# MCU.net
KiCad netlist of a schematic drawn in Altium Designer
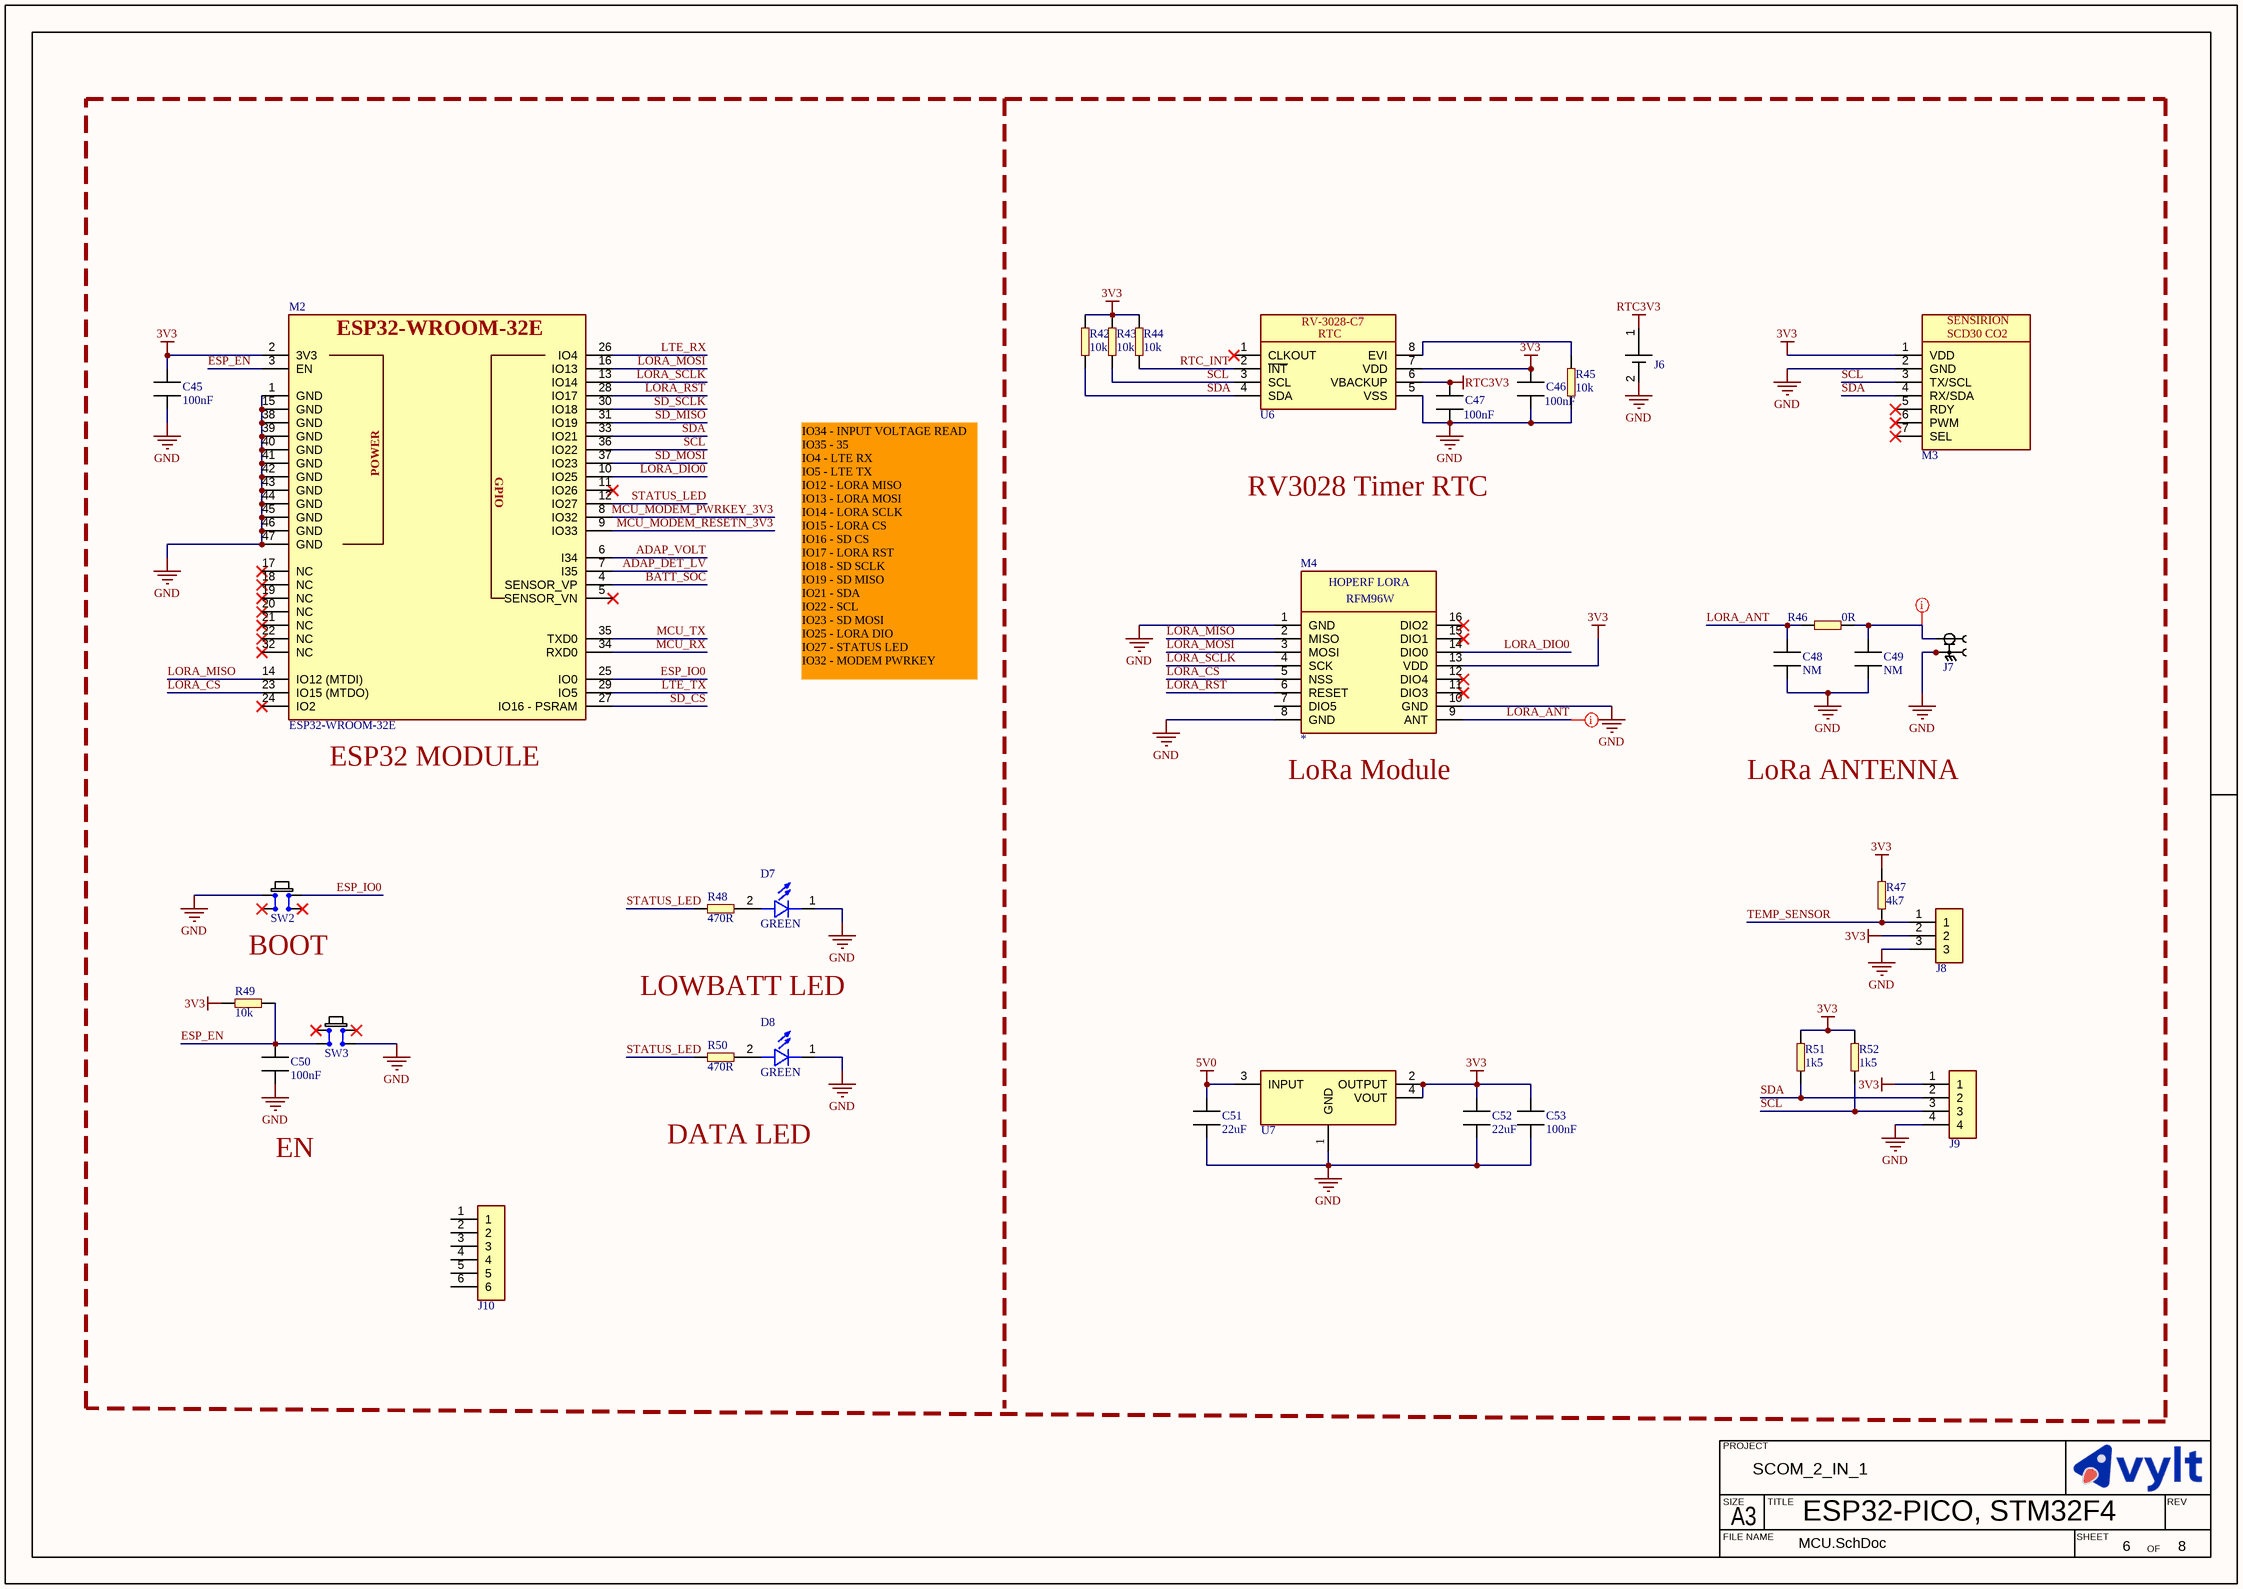
[diagram p0: MCU.SchDoc]

(export (version "E")
  (design (tool "Eeschema 10.0.6"))
  (components
    (comp (ref "C45")
      (value "100nF")
      (footprint "CAPC2012X13L")
      (description "Chip Capacitor, 2-Leads, Body 2.00x1.25mm, IPC High Density")
      (fields (field (name "Comment") "MLCC_0805"))
      (libsource (lib "Capacitor") (part "MLCC_0805"))
    )
    (comp (ref "C46")
      (value "100nF")
      (footprint "CAPC2012X13L")
      (description "1uF 105 0805 (2012 metric) 50V X7R MLCC SMD")
      (fields (field (name "Comment") "MLCC_0805"))
      (libsource (lib "Capacitor") (part "MLCC_0805"))
    )
    (comp (ref "C47")
      (value "100nF")
      (footprint "CAPC2012X13L")
      (description "1uF 105 0805 (2012 metric) 50V X7R MLCC SMD")
      (fields (field (name "Comment") "MLCC_0805"))
      (libsource (lib "Capacitor") (part "MLCC_0805"))
    )
    (comp (ref "C48")
      (value "NM")
      (footprint "CAPC0603X03L")
      (description "Chip Capacitor, 2-Leads, Body 0.60x0.30mm, IPC High Density")
      (fields (field (name "Comment") "ERP_102-1"))
      (libsource (lib "Capacitor") (part "MLCC_0201"))
    )
    (comp (ref "C49")
      (value "NM")
      (footprint "CAPC0603X03L")
      (description "Chip Capacitor, 2-Leads, Body 0.60x0.30mm, IPC High Density")
      (fields (field (name "Comment") "ERP_102-1"))
      (libsource (lib "Capacitor") (part "MLCC_0201"))
    )
    (comp (ref "C50")
      (value "100nF")
      (footprint "CAPC2012X13L")
      (description "Chip Capacitor, 2-Leads, Body 2.00x1.25mm, IPC High Density")
      (fields (field (name "Comment") "MLCC_0805"))
      (libsource (lib "Capacitor") (part "MLCC_0805"))
    )
    (comp (ref "C51")
      (value "22uF")
      (footprint "CAPC2012X13L")
      (description "Chip Capacitor, 2-Leads, Body 2.00x1.25mm, IPC High Density")
      (fields (field (name "Comment") "MLCC_0805"))
      (libsource (lib "Capacitor") (part "MLCC_0805"))
    )
    (comp (ref "C52")
      (value "22uF")
      (footprint "CAPC2012X13L")
      (description "Chip Capacitor, 2-Leads, Body 2.00x1.25mm, IPC High Density")
      (fields (field (name "Comment") "MLCC_0805"))
      (libsource (lib "Capacitor") (part "MLCC_0805"))
    )
    (comp (ref "C53")
      (value "100nF")
      (footprint "CAPC2012X13L")
      (description "Chip Capacitor, 2-Leads, Body 2.00x1.25mm, IPC High Density")
      (fields (field (name "Comment") "MLCC_0805"))
      (libsource (lib "Capacitor") (part "MLCC_0805"))
    )
    (comp (ref "D7")
      (value "GREEN")
      (footprint "LED_1206")
      (description "LED CLEAR 1206 SMD")
      (fields (field (name "Comment") "LED_1206"))
      (libsource (lib "LED") (part "LED_1206"))
    )
    (comp (ref "D8")
      (value "GREEN")
      (footprint "LED_1206")
      (description "LED CLEAR 1206 SMD")
      (fields (field (name "Comment") "LED_1206"))
      (libsource (lib "LED") (part "LED_1206"))
    )
    (comp (ref "J6")
      (value "CR1220-BH")
      (footprint "CR1220-BH")
      (description "BATTERY HOLDER COIN 12.5MM SMD")
      (libsource (lib "Connectors") (part "CR1220-BH"))
    )
    (comp (ref "J7")
      (value "ERP_148-1")
      (footprint "uFL_50R")
      (description "uFL_50R")
      (libsource (lib "RF_Connector") (part "uFL_50R"))
    )
    (comp (ref "J8")
      (value "Terminal_Block_3Pin_5.08P")
      (footprint "TB_PLUG_5.08P_3P")
      (description "6PINS TERMINAL BLOCK 5.08 PITCH")
      (libsource (lib "Connectors") (part "Terminal_Block_3Pin_5.08P"))
    )
    (comp (ref "J9")
      (value "Terminal_Block_4Pin_5.08P")
      (footprint "TB_PLUG_5.08P_4P")
      (description "6PINS TERMINAL BLOCK 5.08 PITCH")
      (libsource (lib "Connectors") (part "Terminal_Block_4Pin_5.08P"))
    )
    (comp (ref "J10")
      (value "ERP_148-2")
      (footprint "6PX1R_F")
      (description "6PX1R Female Header")
      (libsource (lib "PinHeader") (part "6PX1R_F"))
    )
    (comp (ref "M2")
      (value "ESP32-WROOM-32E")
      (footprint "ESP32-WROOM-32UE")
      (description "ESP32-WROOM-32E Module")
      (libsource (lib "ESP") (part "ESP32-WROOM-32E"))
    )
    (comp (ref "M3")
      (value "SCD30")
      (footprint "SCD30")
      (description "CO₂ accuracy of ±(30 ppm + 3% MV) @400-10000 ppm")
      (libsource (lib "TemperatureSensor") (part "SCD30"))
    )
    (comp (ref "M4")
      (value "RFM96W")
      (footprint "RFM96W")
      (description "LoRa 868MHz SX1276 RF Transreceiver Module RFM96W")
      (fields (field (name "ALTIUM_VALUE") "*"))
      (libsource (lib "WirelessModule") (part "RFM96W"))
    )
    (comp (ref "R42")
      (value "10k")
      (footprint "RES_0603")
      (description "RES_0603")
      (fields (field (name "Comment") "ERP_101-1"))
      (libsource (lib "") (part "RES_0603_2"))
    )
    (comp (ref "R43")
      (value "10k")
      (footprint "RES_0603")
      (description "RES_0603")
      (fields (field (name "Comment") "ERP_101-1"))
      (libsource (lib "") (part "RES_0603_2"))
    )
    (comp (ref "R44")
      (value "10k")
      (footprint "RES_0603")
      (description "RES_0603")
      (fields (field (name "Comment") "ERP_101-1"))
      (libsource (lib "") (part "RES_0603_2"))
    )
    (comp (ref "R45")
      (value "10k")
      (footprint "RES_0603")
      (description "RES_0603")
      (fields (field (name "Comment") "ERP_101-1"))
      (libsource (lib "") (part "RES_0603_2"))
    )
    (comp (ref "R46")
      (value "0R")
      (footprint "RESC0603X03L")
      (description "RES_0201")
      (fields (field (name "Comment") "ERP_101-1"))
      (libsource (lib "Resistor") (part "RES_0201"))
    )
    (comp (ref "R47")
      (value "4k7")
      (footprint "RES_0603")
      (description "RES_0603")
      (fields (field (name "Comment") "ERP_101-1"))
      (libsource (lib "") (part "RES_0603_1"))
    )
    (comp (ref "R48")
      (value "470R")
      (footprint "RES_0603")
      (description "RES_0603")
      (fields (field (name "Comment") "ERP_101-1"))
      (libsource (lib "Resistor") (part "RES_0603"))
    )
    (comp (ref "R49")
      (value "10k")
      (footprint "RES_0603")
      (description "RES_0603")
      (fields (field (name "Comment") "ERP_101-1"))
      (libsource (lib "Resistor") (part "RES_0603"))
    )
    (comp (ref "R50")
      (value "470R")
      (footprint "RES_0603")
      (description "RES_0603")
      (fields (field (name "Comment") "ERP_101-1"))
      (libsource (lib "Resistor") (part "RES_0603"))
    )
    (comp (ref "R51")
      (value "1k5")
      (footprint "RES_0603")
      (description "RES_0603")
      (fields (field (name "Comment") "ERP_101-1"))
      (libsource (lib "") (part "RES_0603_1"))
    )
    (comp (ref "R52")
      (value "1k5")
      (footprint "RES_0603")
      (description "RES_0603")
      (fields (field (name "Comment") "ERP_101-1"))
      (libsource (lib "") (part "RES_0603_1"))
    )
    (comp (ref "SW2")
      (value "Generic6X6")
      (footprint "Generic6X6")
      (description "Tactile Switch SPST-NO Top Actuated Surface Mount")
      (libsource (lib "Switch") (part "Generic6X6"))
    )
    (comp (ref "SW3")
      (value "Generic6X6")
      (footprint "Generic6X6")
      (description "Tactile Switch SPST-NO Top Actuated Surface Mount")
      (libsource (lib "Switch") (part "Generic6X6"))
    )
    (comp (ref "U6")
      (value "RV-3028-C7")
      (footprint "RV-3028-C7")
      (description "IC RTC CLK/CALENDAR I2C 8SON")
      (libsource (lib "RTC") (part "RV-3028-C7"))
    )
    (comp (ref "U7")
      (value "ERP_123-1")
      (footprint "AMS1117_SOT223")
      (description "AMS1117 LDO")
      (libsource (lib "VoltageRegulator") (part "AMS1117_SOT223"))
    )
  )
  (nets
    (net (code "1") (name "/ADAP_DET_LV") (class "Default")
      (node (ref "M2") (pin "7") (pinfunction "I35_7") (pintype "passive"))
    )
    (net (code "2") (name "/ADAP_VOLT") (class "Default")
      (node (ref "M2") (pin "6") (pinfunction "I34_6") (pintype "passive"))
    )
    (net (code "3") (name "/BATT_SOC") (class "Default")
      (node (ref "M2") (pin "4") (pinfunction "SENSOR_VP_4") (pintype "passive"))
    )
    (net (code "4") (name "/ESP_EN") (class "Default")
      (node (ref "C50") (pin "1") (pinfunction "1_1") (pintype "passive"))
      (node (ref "M2") (pin "3") (pinfunction "EN_3") (pintype "passive"))
      (node (ref "R49") (pin "1") (pinfunction "1_1") (pintype "passive"))
      (node (ref "SW3") (pin "2") (pinfunction "NO_2") (pintype "passive"))
    )
    (net (code "5") (name "/ESP_IO0") (class "Default")
      (node (ref "M2") (pin "25") (pinfunction "IO0_25") (pintype "passive"))
      (node (ref "SW2") (pin "3") (pinfunction "COM_3") (pintype "passive"))
    )
    (net (code "6") (name "/LORA_ANT") (class "Default")
      (node (ref "C48") (pin "2") (pinfunction "2_2") (pintype "passive"))
      (node (ref "M4") (pin "9") (pinfunction "ANT_9") (pintype "passive"))
      (node (ref "R46") (pin "2") (pinfunction "2_2") (pintype "passive"))
    )
    (net (code "7") (name "/LORA_CS") (class "Default")
      (node (ref "M2") (pin "23") (pinfunction "IO15_(MTDO)_23") (pintype "passive"))
      (node (ref "M4") (pin "5") (pinfunction "NSS_5") (pintype "passive"))
    )
    (net (code "8") (name "/LORA_DIO0") (class "Default")
      (node (ref "M2") (pin "10") (pinfunction "IO25_10") (pintype "passive"))
      (node (ref "M4") (pin "14") (pinfunction "DIO0_14") (pintype "passive"))
    )
    (net (code "9") (name "/LORA_MISO") (class "Default")
      (node (ref "M2") (pin "14") (pinfunction "IO12_(MTDI)_14") (pintype "passive"))
      (node (ref "M4") (pin "2") (pinfunction "MISO_2") (pintype "passive"))
    )
    (net (code "10") (name "/LORA_MOSI") (class "Default")
      (node (ref "M2") (pin "16") (pinfunction "IO13_16") (pintype "passive"))
      (node (ref "M4") (pin "3") (pinfunction "MOSI_3") (pintype "passive"))
    )
    (net (code "11") (name "/LORA_RST") (class "Default")
      (node (ref "M2") (pin "28") (pinfunction "IO17_28") (pintype "passive"))
      (node (ref "M4") (pin "6") (pinfunction "RESET_6") (pintype "passive"))
    )
    (net (code "12") (name "/LORA_SCLK") (class "Default")
      (node (ref "M2") (pin "13") (pinfunction "IO14_13") (pintype "passive"))
      (node (ref "M4") (pin "4") (pinfunction "SCK_4") (pintype "passive"))
    )
    (net (code "13") (name "/LTE_RX") (class "Default")
      (node (ref "M2") (pin "26") (pinfunction "IO4_26") (pintype "passive"))
    )
    (net (code "14") (name "/LTE_TX") (class "Default")
      (node (ref "M2") (pin "29") (pinfunction "IO5_29") (pintype "passive"))
    )
    (net (code "15") (name "/MCU_MODEM_PWRKEY_3V3") (class "Default")
      (node (ref "M2") (pin "8") (pinfunction "IO32_8") (pintype "passive"))
    )
    (net (code "16") (name "/MCU_MODEM_RESETN_3V3") (class "Default")
      (node (ref "M2") (pin "9") (pinfunction "IO33_9") (pintype "passive"))
    )
    (net (code "17") (name "/MCU_RX") (class "Default")
      (node (ref "M2") (pin "34") (pinfunction "RXD0_34") (pintype "passive"))
    )
    (net (code "18") (name "/MCU_TX") (class "Default")
      (node (ref "M2") (pin "35") (pinfunction "TXD0_35") (pintype "passive"))
    )
    (net (code "19") (name "/RTC_INT") (class "Default")
      (node (ref "R44") (pin "1") (pinfunction "1_1") (pintype "passive"))
      (node (ref "U6") (pin "2") (pinfunction "~{INT}_2") (pintype "passive"))
    )
    (net (code "20") (name "/SCL") (class "Default")
      (node (ref "J9") (pin "3") (pinfunction "3_3") (pintype "passive"))
      (node (ref "M2") (pin "36") (pinfunction "IO22_36") (pintype "passive"))
      (node (ref "M3") (pin "3") (pinfunction "TX/SCL_3") (pintype "passive"))
      (node (ref "R43") (pin "1") (pinfunction "1_1") (pintype "passive"))
      (node (ref "R52") (pin "2") (pinfunction "2_2") (pintype "passive"))
      (node (ref "U6") (pin "3") (pinfunction "SCL_3") (pintype "passive"))
    )
    (net (code "21") (name "/SDA") (class "Default")
      (node (ref "J9") (pin "2") (pinfunction "2_2") (pintype "passive"))
      (node (ref "M2") (pin "33") (pinfunction "IO21_33") (pintype "passive"))
      (node (ref "M3") (pin "4") (pinfunction "RX/SDA_4") (pintype "passive"))
      (node (ref "R42") (pin "1") (pinfunction "1_1") (pintype "passive"))
      (node (ref "R51") (pin "2") (pinfunction "2_2") (pintype "passive"))
      (node (ref "U6") (pin "4") (pinfunction "SDA_4") (pintype "passive"))
    )
    (net (code "22") (name "/SD_CS") (class "Default")
      (node (ref "M2") (pin "27") (pinfunction "IO16_-_PSRAM_27") (pintype "passive"))
    )
    (net (code "23") (name "/SD_MISO") (class "Default")
      (node (ref "M2") (pin "31") (pinfunction "IO19_31") (pintype "passive"))
    )
    (net (code "24") (name "/SD_MOSI") (class "Default")
      (node (ref "M2") (pin "37") (pinfunction "IO23_37") (pintype "passive"))
    )
    (net (code "25") (name "/SD_SCLK") (class "Default")
      (node (ref "M2") (pin "30") (pinfunction "IO18_30") (pintype "passive"))
    )
    (net (code "26") (name "/STATUS_LED") (class "Default")
      (node (ref "M2") (pin "12") (pinfunction "IO27_12") (pintype "passive"))
      (node (ref "R48") (pin "2") (pinfunction "2_2") (pintype "passive"))
      (node (ref "R50") (pin "2") (pinfunction "2_2") (pintype "passive"))
    )
    (net (code "27") (name "/TEMP_SENSOR") (class "Default")
      (node (ref "J8") (pin "1") (pinfunction "1_1") (pintype "passive"))
      (node (ref "R47") (pin "2") (pinfunction "2_2") (pintype "passive"))
    )
    (net (code "28") (name "3V3") (class "Default")
      (node (ref "C45") (pin "1") (pinfunction "1_1") (pintype "passive"))
      (node (ref "C46") (pin "1") (pinfunction "1_1") (pintype "passive"))
      (node (ref "C52") (pin "1") (pinfunction "1_1") (pintype "passive"))
      (node (ref "C53") (pin "1") (pinfunction "1_1") (pintype "passive"))
      (node (ref "J8") (pin "2") (pinfunction "2_2") (pintype "passive"))
      (node (ref "J9") (pin "1") (pinfunction "1_1") (pintype "passive"))
      (node (ref "M2") (pin "2") (pinfunction "3V3_2") (pintype "passive"))
      (node (ref "M3") (pin "1") (pinfunction "VDD_1") (pintype "passive"))
      (node (ref "M4") (pin "13") (pinfunction "VDD_13") (pintype "passive"))
      (node (ref "R42") (pin "2") (pinfunction "2_2") (pintype "passive"))
      (node (ref "R43") (pin "2") (pinfunction "2_2") (pintype "passive"))
      (node (ref "R44") (pin "2") (pinfunction "2_2") (pintype "passive"))
      (node (ref "R47") (pin "1") (pinfunction "1_1") (pintype "passive"))
      (node (ref "R49") (pin "2") (pinfunction "2_2") (pintype "passive"))
      (node (ref "R51") (pin "1") (pinfunction "1_1") (pintype "passive"))
      (node (ref "R52") (pin "1") (pinfunction "1_1") (pintype "passive"))
      (node (ref "U6") (pin "7") (pinfunction "VDD_7") (pintype "passive"))
      (node (ref "U7") (pin "2") (pinfunction "OUTPUT_2") (pintype "passive"))
      (node (ref "U7") (pin "4") (pinfunction "VOUT_4") (pintype "passive"))
    )
    (net (code "29") (name "5V0") (class "Default")
      (node (ref "C51") (pin "1") (pinfunction "1_1") (pintype "passive"))
      (node (ref "U7") (pin "3") (pinfunction "INPUT_3") (pintype "passive"))
    )
    (net (code "30") (name "GND") (class "Default")
      (node (ref "C45") (pin "2") (pinfunction "2_2") (pintype "passive"))
      (node (ref "C46") (pin "2") (pinfunction "2_2") (pintype "passive"))
      (node (ref "C47") (pin "2") (pinfunction "2_2") (pintype "passive"))
      (node (ref "C48") (pin "1") (pinfunction "1_1") (pintype "passive"))
      (node (ref "C49") (pin "1") (pinfunction "1_1") (pintype "passive"))
      (node (ref "C50") (pin "2") (pinfunction "2_2") (pintype "passive"))
      (node (ref "C51") (pin "2") (pinfunction "2_2") (pintype "passive"))
      (node (ref "C52") (pin "2") (pinfunction "2_2") (pintype "passive"))
      (node (ref "C53") (pin "2") (pinfunction "2_2") (pintype "passive"))
      (node (ref "D7") (pin "1") (pinfunction "1_1") (pintype "passive"))
      (node (ref "D8") (pin "1") (pinfunction "1_1") (pintype "passive"))
      (node (ref "J6") (pin "2") (pinfunction "-_2") (pintype "passive"))
      (node (ref "J7") (pin "1") (pinfunction "1_1") (pintype "passive"))
      (node (ref "J7") (pin "2") (pinfunction "2_2") (pintype "passive"))
      (node (ref "J8") (pin "3") (pinfunction "3_3") (pintype "passive"))
      (node (ref "J9") (pin "4") (pinfunction "4_4") (pintype "passive"))
      (node (ref "M2") (pin "1") (pinfunction "GND_1") (pintype "passive"))
      (node (ref "M2") (pin "15") (pinfunction "GND_15") (pintype "passive"))
      (node (ref "M2") (pin "38") (pinfunction "GND_38") (pintype "passive"))
      (node (ref "M2") (pin "39") (pinfunction "GND_39") (pintype "passive"))
      (node (ref "M2") (pin "40") (pinfunction "GND_40") (pintype "passive"))
      (node (ref "M2") (pin "41") (pinfunction "GND_41") (pintype "passive"))
      (node (ref "M2") (pin "42") (pinfunction "GND_42") (pintype "passive"))
      (node (ref "M2") (pin "43") (pinfunction "GND_43") (pintype "passive"))
      (node (ref "M2") (pin "44") (pinfunction "GND_44") (pintype "passive"))
      (node (ref "M2") (pin "45") (pinfunction "GND_45") (pintype "passive"))
      (node (ref "M2") (pin "46") (pinfunction "GND_46") (pintype "passive"))
      (node (ref "M2") (pin "47") (pinfunction "GND_47") (pintype "passive"))
      (node (ref "M3") (pin "2") (pinfunction "GND_2") (pintype "passive"))
      (node (ref "M4") (pin "1") (pinfunction "GND_1") (pintype "passive"))
      (node (ref "M4") (pin "10") (pinfunction "GND_10") (pintype "passive"))
      (node (ref "M4") (pin "8") (pinfunction "GND_8") (pintype "passive"))
      (node (ref "R45") (pin "1") (pinfunction "1_1") (pintype "passive"))
      (node (ref "SW2") (pin "1") (pinfunction "NO_1") (pintype "passive"))
      (node (ref "SW3") (pin "4") (pinfunction "COM_4") (pintype "passive"))
      (node (ref "U6") (pin "5") (pinfunction "VSS_5") (pintype "passive"))
      (node (ref "U7") (pin "1") (pinfunction "GND_1") (pintype "power_in"))
    )
    (net (code "31") (name "Net-(C49-Pad2)") (class "Default")
      (node (ref "C49") (pin "2") (pinfunction "2_2") (pintype "passive"))
      (node (ref "J7") (pin "3") (pinfunction "3_3") (pintype "passive"))
      (node (ref "R46") (pin "1") (pinfunction "1_1") (pintype "passive"))
    )
    (net (code "32") (name "Net-(D7-Pad2)") (class "Default")
      (node (ref "D7") (pin "2") (pinfunction "2_2") (pintype "passive"))
      (node (ref "R48") (pin "1") (pinfunction "1_1") (pintype "passive"))
    )
    (net (code "33") (name "Net-(D8-Pad2)") (class "Default")
      (node (ref "D8") (pin "2") (pinfunction "2_2") (pintype "passive"))
      (node (ref "R50") (pin "1") (pinfunction "1_1") (pintype "passive"))
    )
    (net (code "34") (name "Net-(U6-EVI)") (class "Default")
      (node (ref "R45") (pin "2") (pinfunction "2_2") (pintype "passive"))
      (node (ref "U6") (pin "8") (pinfunction "EVI_8") (pintype "passive"))
    )
    (net (code "35") (name "RTC3V3") (class "Default")
      (node (ref "C47") (pin "1") (pinfunction "1_1") (pintype "passive"))
      (node (ref "J6") (pin "1") (pinfunction "+_1") (pintype "passive"))
      (node (ref "U6") (pin "6") (pinfunction "VBACKUP_6") (pintype "passive"))
    )
    (net (code "36") (name "unconnected-(J10-Pad1)") (class "Default")
      (node (ref "J10") (pin "1") (pinfunction "1_1") (pintype "passive"))
    )
    (net (code "37") (name "unconnected-(J10-Pad2)") (class "Default")
      (node (ref "J10") (pin "2") (pinfunction "2_2") (pintype "passive"))
    )
    (net (code "38") (name "unconnected-(J10-Pad3)") (class "Default")
      (node (ref "J10") (pin "3") (pinfunction "3_3") (pintype "passive"))
    )
    (net (code "39") (name "unconnected-(J10-Pad4)") (class "Default")
      (node (ref "J10") (pin "4") (pinfunction "4_4") (pintype "passive"))
    )
    (net (code "40") (name "unconnected-(J10-Pad5)") (class "Default")
      (node (ref "J10") (pin "5") (pinfunction "5_5") (pintype "passive"))
    )
    (net (code "41") (name "unconnected-(J10-Pad6)") (class "Default")
      (node (ref "J10") (pin "6") (pinfunction "6_6") (pintype "passive"))
    )
    (net (code "42") (name "unconnected-(M2-IO2-Pad24)") (class "Default")
      (node (ref "M2") (pin "24") (pinfunction "IO2_24") (pintype "passive+no_connect"))
    )
    (net (code "43") (name "unconnected-(M2-IO26-Pad11)") (class "Default")
      (node (ref "M2") (pin "11") (pinfunction "IO26_11") (pintype "passive+no_connect"))
    )
    (net (code "44") (name "unconnected-(M2-NC-Pad17)") (class "Default")
      (node (ref "M2") (pin "17") (pinfunction "NC_17") (pintype "passive+no_connect"))
    )
    (net (code "45") (name "unconnected-(M2-NC-Pad18)") (class "Default")
      (node (ref "M2") (pin "18") (pinfunction "NC_18") (pintype "passive+no_connect"))
    )
    (net (code "46") (name "unconnected-(M2-NC-Pad19)") (class "Default")
      (node (ref "M2") (pin "19") (pinfunction "NC_19") (pintype "passive+no_connect"))
    )
    (net (code "47") (name "unconnected-(M2-NC-Pad20)") (class "Default")
      (node (ref "M2") (pin "20") (pinfunction "NC_20") (pintype "passive+no_connect"))
    )
    (net (code "48") (name "unconnected-(M2-NC-Pad21)") (class "Default")
      (node (ref "M2") (pin "21") (pinfunction "NC_21") (pintype "passive+no_connect"))
    )
    (net (code "49") (name "unconnected-(M2-NC-Pad22)") (class "Default")
      (node (ref "M2") (pin "22") (pinfunction "NC_22") (pintype "passive+no_connect"))
    )
    (net (code "50") (name "unconnected-(M2-NC-Pad32)") (class "Default")
      (node (ref "M2") (pin "32") (pinfunction "NC_32") (pintype "passive+no_connect"))
    )
    (net (code "51") (name "unconnected-(M2-SENSOR_VN-Pad5)") (class "Default")
      (node (ref "M2") (pin "5") (pinfunction "SENSOR_VN_5") (pintype "passive+no_connect"))
    )
    (net (code "52") (name "unconnected-(M3-PWM-Pad6)") (class "Default")
      (node (ref "M3") (pin "6") (pinfunction "PWM_6") (pintype "passive+no_connect"))
    )
    (net (code "53") (name "unconnected-(M3-RDY-Pad5)") (class "Default")
      (node (ref "M3") (pin "5") (pinfunction "RDY_5") (pintype "passive+no_connect"))
    )
    (net (code "54") (name "unconnected-(M3-SEL-Pad7)") (class "Default")
      (node (ref "M3") (pin "7") (pinfunction "SEL_7") (pintype "passive+no_connect"))
    )
    (net (code "55") (name "unconnected-(M4-DIO1-Pad15)") (class "Default")
      (node (ref "M4") (pin "15") (pinfunction "DIO1_15") (pintype "passive+no_connect"))
    )
    (net (code "56") (name "unconnected-(M4-DIO2-Pad16)") (class "Default")
      (node (ref "M4") (pin "16") (pinfunction "DIO2_16") (pintype "passive+no_connect"))
    )
    (net (code "57") (name "unconnected-(M4-DIO3-Pad11)") (class "Default")
      (node (ref "M4") (pin "11") (pinfunction "DIO3_11") (pintype "passive+no_connect"))
    )
    (net (code "58") (name "unconnected-(M4-DIO4-Pad12)") (class "Default")
      (node (ref "M4") (pin "12") (pinfunction "DIO4_12") (pintype "passive+no_connect"))
    )
    (net (code "59") (name "unconnected-(M4-DIO5-Pad7)") (class "Default")
      (node (ref "M4") (pin "7") (pinfunction "DIO5_7") (pintype "passive"))
    )
    (net (code "60") (name "unconnected-(SW2-COM-Pad4)") (class "Default")
      (node (ref "SW2") (pin "4") (pinfunction "COM_4") (pintype "passive+no_connect"))
    )
    (net (code "61") (name "unconnected-(SW2-NO-Pad2)") (class "Default")
      (node (ref "SW2") (pin "2") (pinfunction "NO_2") (pintype "passive+no_connect"))
    )
    (net (code "62") (name "unconnected-(SW3-COM-Pad3)") (class "Default")
      (node (ref "SW3") (pin "3") (pinfunction "COM_3") (pintype "passive+no_connect"))
    )
    (net (code "63") (name "unconnected-(SW3-NO-Pad1)") (class "Default")
      (node (ref "SW3") (pin "1") (pinfunction "NO_1") (pintype "passive+no_connect"))
    )
    (net (code "64") (name "unconnected-(U6-CLKOUT-Pad1)") (class "Default")
      (node (ref "U6") (pin "1") (pinfunction "CLKOUT_1") (pintype "passive+no_connect"))
    )
  )
)
